# InputCircuits1.net
KiCad netlist of a schematic drawn in Altium Designer
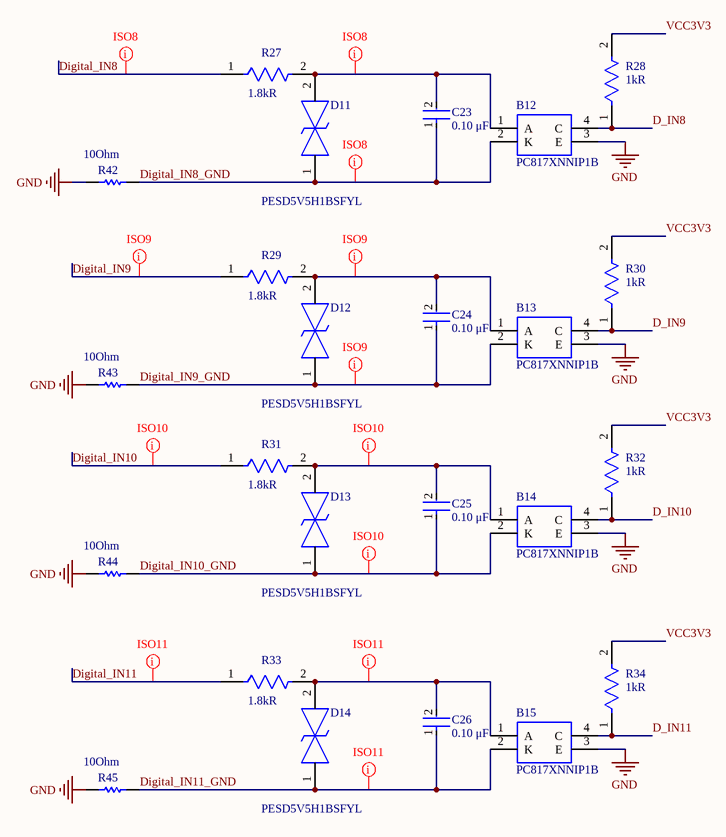
[diagram p0: InputCircuits1.SchDoc]

(export (version "E")
  (design (tool "Eeschema 10.0.6"))
  (components
    (comp (ref "B12")
      (value "PC817XNNIP1B")
      (footprint "SOP254P960X420-4N")
      (description "Transistor Output Optocouplers Photocoupler")
      (fields (field (name "MOUSER PART NUMBER") "852-PC817XNNIP1B"))
      (libsource (lib "Schlib2") (part "PC817XNNIP1B"))
    )
    (comp (ref "B13")
      (value "PC817XNNIP1B")
      (footprint "SOP254P960X420-4N")
      (description "Transistor Output Optocouplers Photocoupler")
      (fields (field (name "MOUSER PART NUMBER") "852-PC817XNNIP1B"))
      (libsource (lib "Schlib2") (part "PC817XNNIP1B"))
    )
    (comp (ref "B14")
      (value "PC817XNNIP1B")
      (footprint "SOP254P960X420-4N")
      (description "Transistor Output Optocouplers Photocoupler")
      (fields (field (name "MOUSER PART NUMBER") "852-PC817XNNIP1B"))
      (libsource (lib "Schlib2") (part "PC817XNNIP1B"))
    )
    (comp (ref "B15")
      (value "PC817XNNIP1B")
      (footprint "SOP254P960X420-4N")
      (description "Transistor Output Optocouplers Photocoupler")
      (fields (field (name "MOUSER PART NUMBER") "852-PC817XNNIP1B"))
      (libsource (lib "Schlib2") (part "PC817XNNIP1B"))
    )
    (comp (ref "C23")
      (value "0.10 μF")
      (footprint "FP-C0805C-DN-MFG")
      (description "C0805 0.10 μF X7R 30ppm/°C 10.00% 50 V")
      (fields
        (field (name "MANUFACTURER") "KEMET")
        (field (name "MANUFACTURER PART NUMBER") "C0805C104K5RAC7411")
      )
      (libsource (lib "Altium Content Vault") (part "b4654b650e69147ec39a6b967a45e02"))
    )
    (comp (ref "C24")
      (value "0.10 μF")
      (footprint "FP-C0805C-DN-MFG")
      (description "C0805 0.10 μF X7R 30ppm/°C 10.00% 50 V")
      (fields
        (field (name "MANUFACTURER") "KEMET")
        (field (name "MANUFACTURER PART NUMBER") "C0805C104K5RAC7411")
      )
      (libsource (lib "Altium Content Vault") (part "b4654b650e69147ec39a6b967a45e02"))
    )
    (comp (ref "C25")
      (value "0.10 μF")
      (footprint "FP-C0805C-DN-MFG")
      (description "C0805 0.10 μF X7R 30ppm/°C 10.00% 50 V")
      (fields
        (field (name "MANUFACTURER") "KEMET")
        (field (name "MANUFACTURER PART NUMBER") "C0805C104K5RAC7411")
      )
      (libsource (lib "Altium Content Vault") (part "b4654b650e69147ec39a6b967a45e02"))
    )
    (comp (ref "C26")
      (value "0.10 μF")
      (footprint "FP-C0805C-DN-MFG")
      (description "C0805 0.10 μF X7R 30ppm/°C 10.00% 50 V")
      (fields
        (field (name "MANUFACTURER") "KEMET")
        (field (name "MANUFACTURER PART NUMBER") "C0805C104K5RAC7411")
      )
      (libsource (lib "Altium Content Vault") (part "b4654b650e69147ec39a6b967a45e02"))
    )
    (comp (ref "D11")
      (value "PESD5V5H1BSFYL")
      (footprint "PESD5V0H1BSFYL")
      (description "ESD Suppressors / TVS Diodes")
      (fields (field (name "MOUSER PART NUMBER") "771-PESD5V5H1BSFYL"))
      (libsource (lib "Schlib2") (part "PESD5V5H1BSFYL"))
    )
    (comp (ref "D12")
      (value "PESD5V5H1BSFYL")
      (footprint "PESD5V0H1BSFYL")
      (description "ESD Suppressors / TVS Diodes")
      (fields (field (name "MOUSER PART NUMBER") "771-PESD5V5H1BSFYL"))
      (libsource (lib "Schlib2") (part "PESD5V5H1BSFYL"))
    )
    (comp (ref "D13")
      (value "PESD5V5H1BSFYL")
      (footprint "PESD5V0H1BSFYL")
      (description "ESD Suppressors / TVS Diodes")
      (fields (field (name "MOUSER PART NUMBER") "771-PESD5V5H1BSFYL"))
      (libsource (lib "Schlib2") (part "PESD5V5H1BSFYL"))
    )
    (comp (ref "D14")
      (value "PESD5V5H1BSFYL")
      (footprint "PESD5V0H1BSFYL")
      (description "ESD Suppressors / TVS Diodes")
      (fields (field (name "MOUSER PART NUMBER") "771-PESD5V5H1BSFYL"))
      (libsource (lib "Schlib2") (part "PESD5V5H1BSFYL"))
    )
    (comp (ref "R27")
      (value "RC0603FR-071K8L")
      (footprint "FP-RC0603-0_55-IPC_C")
      (description "RES SMD 1.8K OHM 1% 1/10W 0603")
      (fields (field (name "TOLERANCE") "1%") (field (name "RESISTANCE") "1.8kR"))
      (libsource (lib "Altium Content Vault") (part "1029c3af85768c4190bb7ad29bc67b5"))
    )
    (comp (ref "R28")
      (value "RC0603FR-071KL")
      (footprint "FP-RC0603-0_55-IPC_C")
      (description "RES 1K OHM 1% 1/10W 0603")
      (fields (field (name "RESISTANCE") "1kR") (field (name "TOLERANCE") "1%"))
      (libsource (lib "Altium Content Vault") (part "1029c3af85768c4190bb7ad29bc67b5"))
    )
    (comp (ref "R29")
      (value "RC0603FR-071K8L")
      (footprint "FP-RC0603-0_55-IPC_C")
      (description "RES SMD 1.8K OHM 1% 1/10W 0603")
      (fields (field (name "TOLERANCE") "1%") (field (name "RESISTANCE") "1.8kR"))
      (libsource (lib "Altium Content Vault") (part "1029c3af85768c4190bb7ad29bc67b5"))
    )
    (comp (ref "R30")
      (value "RC0603FR-071KL")
      (footprint "FP-RC0603-0_55-IPC_C")
      (description "RES 1K OHM 1% 1/10W 0603")
      (fields (field (name "RESISTANCE") "1kR") (field (name "TOLERANCE") "1%"))
      (libsource (lib "Altium Content Vault") (part "1029c3af85768c4190bb7ad29bc67b5"))
    )
    (comp (ref "R31")
      (value "RC0603FR-071K8L")
      (footprint "FP-RC0603-0_55-IPC_C")
      (description "RES SMD 1.8K OHM 1% 1/10W 0603")
      (fields (field (name "TOLERANCE") "1%") (field (name "RESISTANCE") "1.8kR"))
      (libsource (lib "Altium Content Vault") (part "1029c3af85768c4190bb7ad29bc67b5"))
    )
    (comp (ref "R32")
      (value "RC0603FR-071KL")
      (footprint "FP-RC0603-0_55-IPC_C")
      (description "RES 1K OHM 1% 1/10W 0603")
      (fields (field (name "RESISTANCE") "1kR") (field (name "TOLERANCE") "1%"))
      (libsource (lib "Altium Content Vault") (part "1029c3af85768c4190bb7ad29bc67b5"))
    )
    (comp (ref "R33")
      (value "RC0603FR-071K8L")
      (footprint "FP-RC0603-0_55-IPC_C")
      (description "RES SMD 1.8K OHM 1% 1/10W 0603")
      (fields (field (name "TOLERANCE") "1%") (field (name "RESISTANCE") "1.8kR"))
      (libsource (lib "Altium Content Vault") (part "1029c3af85768c4190bb7ad29bc67b5"))
    )
    (comp (ref "R34")
      (value "RC0603FR-071KL")
      (footprint "FP-RC0603-0_55-IPC_C")
      (description "RES 1K OHM 1% 1/10W 0603")
      (fields (field (name "RESISTANCE") "1kR") (field (name "TOLERANCE") "1%"))
      (libsource (lib "Altium Content Vault") (part "1029c3af85768c4190bb7ad29bc67b5"))
    )
    (comp (ref "R42")
      (value "RC0805FR-0710RL")
      (footprint "RESC2013X60X35ML10T20")
      (description "Chip Resistor, 10 Ohm, +/- 1%, 0.125 W, -55 to 155 degC, 0805 (2012 Metric), RoHS, Tape and Reel")
      (fields
        (field (name "RESISTANCE") "10Ohm")
        (field (name "MANUFACTURER") "Yageo")
        (field (name "TOLERANCE") "1%")
      )
      (libsource (lib "Altium Content Vault") (part "RES-2"))
    )
    (comp (ref "R43")
      (value "RC0805FR-0710RL")
      (footprint "RESC2013X60X35ML10T20")
      (description "Chip Resistor, 10 Ohm, +/- 1%, 0.125 W, -55 to 155 degC, 0805 (2012 Metric), RoHS, Tape and Reel")
      (fields
        (field (name "RESISTANCE") "10Ohm")
        (field (name "MANUFACTURER") "Yageo")
        (field (name "TOLERANCE") "1%")
      )
      (libsource (lib "Altium Content Vault") (part "RES-2"))
    )
    (comp (ref "R44")
      (value "RC0805FR-0710RL")
      (footprint "RESC2013X60X35ML10T20")
      (description "Chip Resistor, 10 Ohm, +/- 1%, 0.125 W, -55 to 155 degC, 0805 (2012 Metric), RoHS, Tape and Reel")
      (fields
        (field (name "RESISTANCE") "10Ohm")
        (field (name "MANUFACTURER") "Yageo")
        (field (name "TOLERANCE") "1%")
      )
      (libsource (lib "Altium Content Vault") (part "RES-2"))
    )
    (comp (ref "R45")
      (value "RC0805FR-0710RL")
      (footprint "RESC2013X60X35ML10T20")
      (description "Chip Resistor, 10 Ohm, +/- 1%, 0.125 W, -55 to 155 degC, 0805 (2012 Metric), RoHS, Tape and Reel")
      (fields
        (field (name "RESISTANCE") "10Ohm")
        (field (name "MANUFACTURER") "Yageo")
        (field (name "TOLERANCE") "1%")
      )
      (libsource (lib "Altium Content Vault") (part "RES-2"))
    )
  )
  (nets
    (net (code "1") (name "/D_IN8") (class "Default")
      (node (ref "B12") (pin "4") (pinfunction "C_4") (pintype "passive"))
      (node (ref "R28") (pin "1") (pinfunction "1_1") (pintype "passive"))
    )
    (net (code "2") (name "/D_IN9") (class "Default")
      (node (ref "B13") (pin "4") (pinfunction "C_4") (pintype "passive"))
      (node (ref "R30") (pin "1") (pinfunction "1_1") (pintype "passive"))
    )
    (net (code "3") (name "/D_IN10") (class "Default")
      (node (ref "B14") (pin "4") (pinfunction "C_4") (pintype "passive"))
      (node (ref "R32") (pin "1") (pinfunction "1_1") (pintype "passive"))
    )
    (net (code "4") (name "/D_IN11") (class "Default")
      (node (ref "B15") (pin "4") (pinfunction "C_4") (pintype "passive"))
      (node (ref "R34") (pin "1") (pinfunction "1_1") (pintype "passive"))
    )
    (net (code "5") (name "/Digital_IN8") (class "Default")
      (node (ref "R27") (pin "1") (pinfunction "1_1") (pintype "passive"))
    )
    (net (code "6") (name "/Digital_IN8_GND") (class "Default")
      (node (ref "B12") (pin "2") (pinfunction "K_2") (pintype "passive"))
      (node (ref "C23") (pin "1") (pinfunction "1_1") (pintype "passive"))
      (node (ref "D11") (pin "1") (pinfunction "1_1") (pintype "passive"))
      (node (ref "R42") (pin "2") (pinfunction "2_2") (pintype "passive"))
    )
    (net (code "7") (name "/Digital_IN9") (class "Default")
      (node (ref "R29") (pin "1") (pinfunction "1_1") (pintype "passive"))
    )
    (net (code "8") (name "/Digital_IN9_GND") (class "Default")
      (node (ref "B13") (pin "2") (pinfunction "K_2") (pintype "passive"))
      (node (ref "C24") (pin "1") (pinfunction "1_1") (pintype "passive"))
      (node (ref "D12") (pin "1") (pinfunction "1_1") (pintype "passive"))
      (node (ref "R43") (pin "2") (pinfunction "2_2") (pintype "passive"))
    )
    (net (code "9") (name "/Digital_IN10") (class "Default")
      (node (ref "R31") (pin "1") (pinfunction "1_1") (pintype "passive"))
    )
    (net (code "10") (name "/Digital_IN10_GND") (class "Default")
      (node (ref "B14") (pin "2") (pinfunction "K_2") (pintype "passive"))
      (node (ref "C25") (pin "1") (pinfunction "1_1") (pintype "passive"))
      (node (ref "D13") (pin "1") (pinfunction "1_1") (pintype "passive"))
      (node (ref "R44") (pin "2") (pinfunction "2_2") (pintype "passive"))
    )
    (net (code "11") (name "/Digital_IN11") (class "Default")
      (node (ref "R33") (pin "1") (pinfunction "1_1") (pintype "passive"))
    )
    (net (code "12") (name "/Digital_IN11_GND") (class "Default")
      (node (ref "B15") (pin "2") (pinfunction "K_2") (pintype "passive"))
      (node (ref "C26") (pin "1") (pinfunction "1_1") (pintype "passive"))
      (node (ref "D14") (pin "1") (pinfunction "1_1") (pintype "passive"))
      (node (ref "R45") (pin "2") (pinfunction "2_2") (pintype "passive"))
    )
    (net (code "13") (name "/VCC3V3") (class "Default")
      (node (ref "R28") (pin "2") (pinfunction "2_2") (pintype "passive"))
      (node (ref "R30") (pin "2") (pinfunction "2_2") (pintype "passive"))
      (node (ref "R32") (pin "2") (pinfunction "2_2") (pintype "passive"))
      (node (ref "R34") (pin "2") (pinfunction "2_2") (pintype "passive"))
    )
    (net (code "14") (name "GND") (class "Default")
      (node (ref "B12") (pin "3") (pinfunction "E_3") (pintype "passive"))
      (node (ref "B13") (pin "3") (pinfunction "E_3") (pintype "passive"))
      (node (ref "B14") (pin "3") (pinfunction "E_3") (pintype "passive"))
      (node (ref "B15") (pin "3") (pinfunction "E_3") (pintype "passive"))
      (node (ref "R42") (pin "1") (pinfunction "1_1") (pintype "passive"))
      (node (ref "R43") (pin "1") (pinfunction "1_1") (pintype "passive"))
      (node (ref "R44") (pin "1") (pinfunction "1_1") (pintype "passive"))
      (node (ref "R45") (pin "1") (pinfunction "1_1") (pintype "passive"))
    )
    (net (code "15") (name "Net-(B12-A)") (class "Default")
      (node (ref "B12") (pin "1") (pinfunction "A_1") (pintype "passive"))
      (node (ref "C23") (pin "2") (pinfunction "2_2") (pintype "passive"))
      (node (ref "D11") (pin "2") (pinfunction "2_2") (pintype "passive"))
      (node (ref "R27") (pin "2") (pinfunction "2_2") (pintype "passive"))
    )
    (net (code "16") (name "Net-(B13-A)") (class "Default")
      (node (ref "B13") (pin "1") (pinfunction "A_1") (pintype "passive"))
      (node (ref "C24") (pin "2") (pinfunction "2_2") (pintype "passive"))
      (node (ref "D12") (pin "2") (pinfunction "2_2") (pintype "passive"))
      (node (ref "R29") (pin "2") (pinfunction "2_2") (pintype "passive"))
    )
    (net (code "17") (name "Net-(B14-A)") (class "Default")
      (node (ref "B14") (pin "1") (pinfunction "A_1") (pintype "passive"))
      (node (ref "C25") (pin "2") (pinfunction "2_2") (pintype "passive"))
      (node (ref "D13") (pin "2") (pinfunction "2_2") (pintype "passive"))
      (node (ref "R31") (pin "2") (pinfunction "2_2") (pintype "passive"))
    )
    (net (code "18") (name "Net-(B15-A)") (class "Default")
      (node (ref "B15") (pin "1") (pinfunction "A_1") (pintype "passive"))
      (node (ref "C26") (pin "2") (pinfunction "2_2") (pintype "passive"))
      (node (ref "D14") (pin "2") (pinfunction "2_2") (pintype "passive"))
      (node (ref "R33") (pin "2") (pinfunction "2_2") (pintype "passive"))
    )
  )
)
